# electricRayBot2.net
KiCad netlist of a schematic drawn in EAGLE
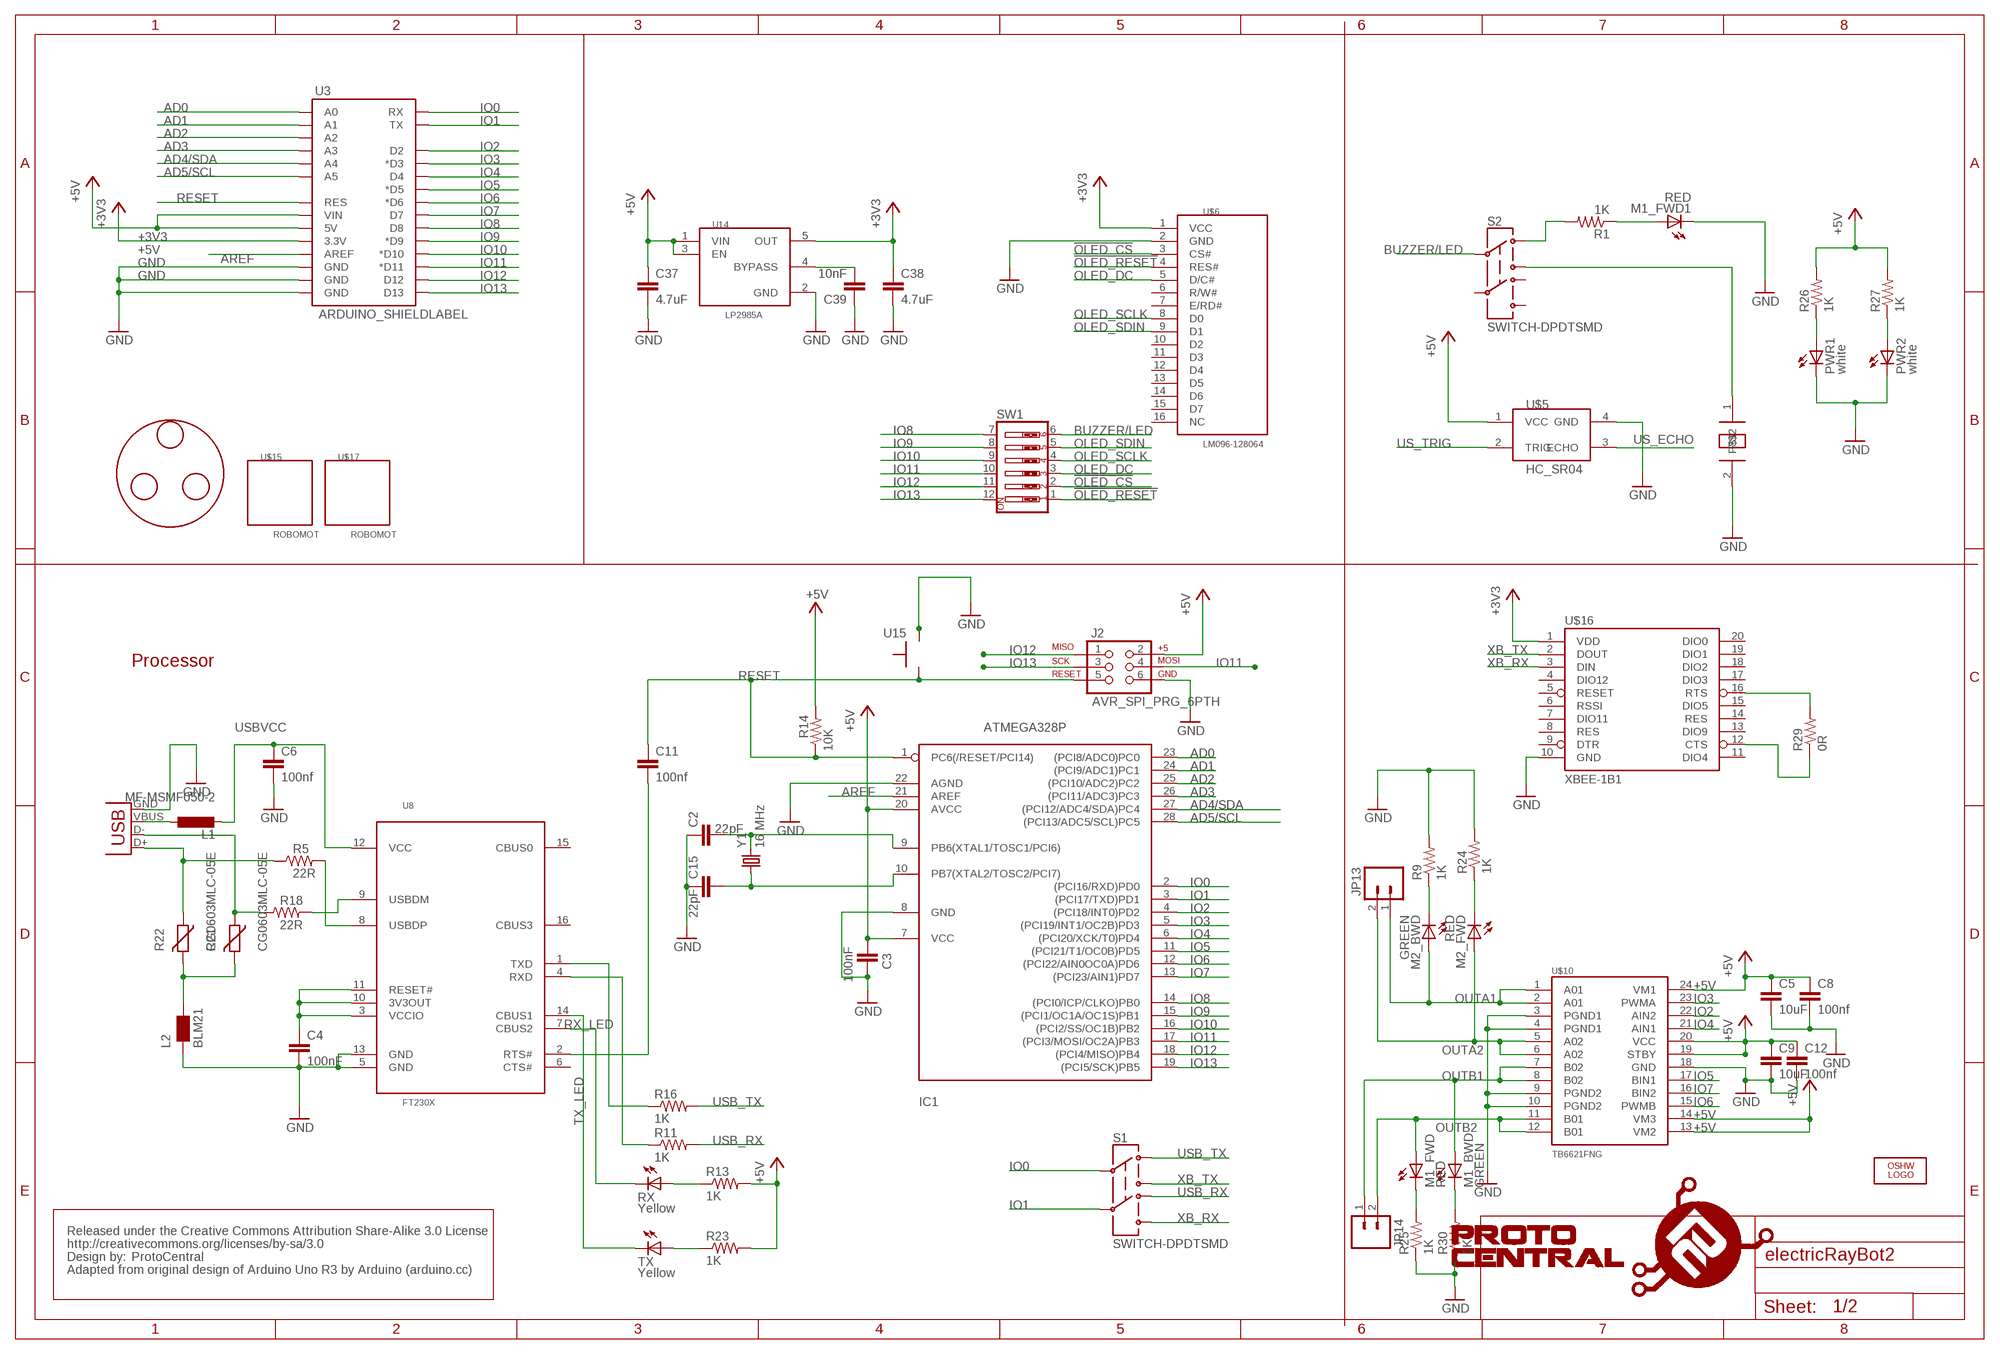
[diagram p0: schematic, sheet 1]
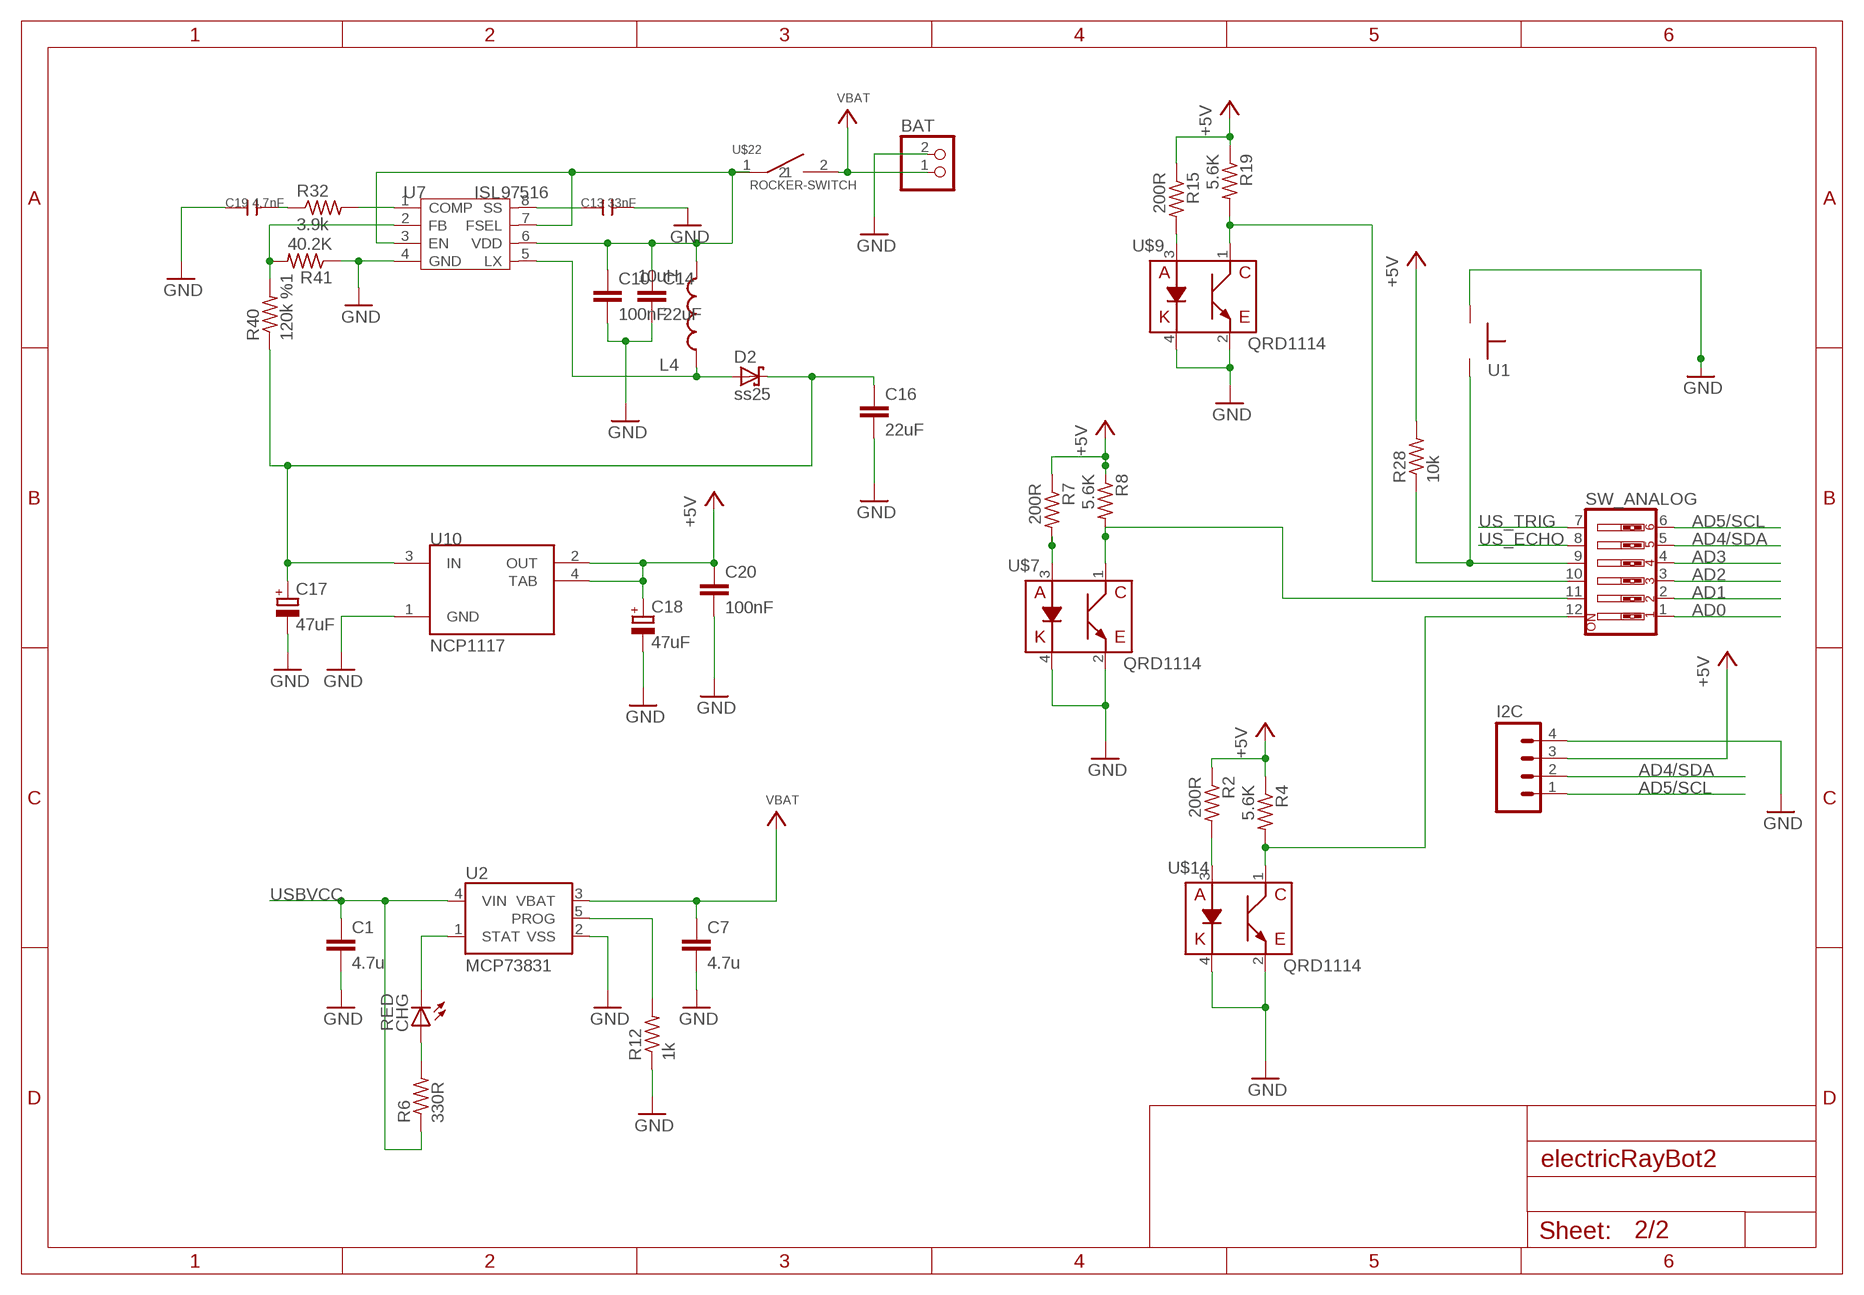
[diagram p1: schematic, sheet 2]

(export (version "E")
  (design (tool "Eeschema 10.0.6"))
  (components
    (comp (ref "BAT")
      (value "JST_2PIN-THM")
      (footprint "eagle-import:JST-PH-2-THM")
      (libsource (lib "eagle-import") (part "JST_2PIN-THM"))
    )
    (comp (ref "C1")
      (value "4.7u")
      (footprint "eagle-import:C0805")
      (libsource (lib "eagle-import") (part "C-EUC0805"))
    )
    (comp (ref "C7")
      (value "4.7u")
      (footprint "eagle-import:C0805")
      (libsource (lib "eagle-import") (part "C-EUC0805"))
    )
    (comp (ref "C10")
      (value "100nF")
      (footprint "eagle-import:C0805")
      (libsource (lib "eagle-import") (part "C-EUC0805"))
    )
    (comp (ref "C13")
      (value "33nF")
      (footprint "eagle-import:C0603")
      (libsource (lib "eagle-import") (part "C-0603"))
    )
    (comp (ref "C14")
      (value "22uF")
      (footprint "eagle-import:C1206")
      (libsource (lib "eagle-import") (part "C-EUC1206"))
    )
    (comp (ref "C16")
      (value "22uF")
      (footprint "eagle-import:C1206")
      (libsource (lib "eagle-import") (part "C-EUC1206"))
    )
    (comp (ref "C17")
      (value "47uF")
      (footprint "eagle-import:PANASONIC_D")
      (libsource (lib "eagle-import") (part "CPOL-EUD"))
    )
    (comp (ref "C18")
      (value "47uF")
      (footprint "eagle-import:PANASONIC_D")
      (libsource (lib "eagle-import") (part "CPOL-EUD"))
    )
    (comp (ref "C19")
      (value "4.7nF")
      (footprint "eagle-import:C0603")
      (libsource (lib "eagle-import") (part "C-0603"))
    )
    (comp (ref "C20")
      (value "100nF")
      (footprint "eagle-import:C0402")
      (libsource (lib "eagle-import") (part "C-EUC0402"))
    )
    (comp (ref "CHG")
      (value "RED")
      (footprint "eagle-import:CHIPLED_0603")
      (libsource (lib "eagle-import") (part "LEDCHIPLED_0603"))
    )
    (comp (ref "D2")
      (value "ss25")
      (footprint "eagle-import:SMB")
      (libsource (lib "eagle-import") (part "SCHOTTKY-DIODESMD"))
    )
    (comp (ref "I2C")
      (value "M04POLAR_LOCK")
      (footprint "eagle-import:MOLEX-1X4_LOCK")
      (libsource (lib "eagle-import") (part "M04POLAR_LOCK"))
    )
    (comp (ref "L4")
      (value "10uH")
      (footprint "eagle-import:CDRH8D43")
      (libsource (lib "eagle-import") (part "CDRH8D43"))
    )
    (comp (ref "R2")
      (value "200R")
      (footprint "eagle-import:R0805")
      (libsource (lib "eagle-import") (part "R-US_R0805"))
    )
    (comp (ref "R4")
      (value "5.6K")
      (footprint "eagle-import:R0805")
      (libsource (lib "eagle-import") (part "R-US_R0805"))
    )
    (comp (ref "R6")
      (value "330R")
      (footprint "eagle-import:R0805")
      (libsource (lib "eagle-import") (part "R-US_R0805"))
    )
    (comp (ref "R7")
      (value "200R")
      (footprint "eagle-import:R0805")
      (libsource (lib "eagle-import") (part "R-US_R0805"))
    )
    (comp (ref "R8")
      (value "5.6K")
      (footprint "eagle-import:R0805")
      (libsource (lib "eagle-import") (part "R-US_R0805"))
    )
    (comp (ref "R12")
      (value "1k")
      (footprint "eagle-import:R0805")
      (libsource (lib "eagle-import") (part "R-US_R0805"))
    )
    (comp (ref "R15")
      (value "200R")
      (footprint "eagle-import:R0805")
      (libsource (lib "eagle-import") (part "R-US_R0805"))
    )
    (comp (ref "R19")
      (value "5.6K")
      (footprint "eagle-import:R0805")
      (libsource (lib "eagle-import") (part "R-US_R0805"))
    )
    (comp (ref "R28")
      (value "10k")
      (footprint "eagle-import:R0805")
      (libsource (lib "eagle-import") (part "R-US_R0805"))
    )
    (comp (ref "R32")
      (value "3.9k")
      (footprint "eagle-import:R0805")
      (libsource (lib "eagle-import") (part "R-US_R0805"))
    )
    (comp (ref "R40")
      (value "120k %1")
      (footprint "eagle-import:R0805")
      (libsource (lib "eagle-import") (part "R-US_R0805"))
    )
    (comp (ref "R41")
      (value "40.2K")
      (footprint "eagle-import:R0805")
      (libsource (lib "eagle-import") (part "R-US_R0805"))
    )
    (comp (ref "SW_ANALOG")
      (value "SW_DIP-6")
      (footprint "eagle-import:EDG-06")
      (libsource (lib "eagle-import") (part "SW_DIP-6"))
    )
    (comp (ref "U$7")
      (value "QRD1114")
      (footprint "eagle-import:QRD1114")
      (libsource (lib "eagle-import") (part "QRD1114"))
    )
    (comp (ref "U$9")
      (value "QRD1114")
      (footprint "eagle-import:QRD1114")
      (libsource (lib "eagle-import") (part "QRD1114"))
    )
    (comp (ref "U$14")
      (value "QRD1114")
      (footprint "eagle-import:QRD1114")
      (libsource (lib "eagle-import") (part "QRD1114"))
    )
    (comp (ref "U$22")
      (value "ROCKER-SWITCH")
      (footprint "eagle-import:SPST(RIGHT-ANGLE)")
      (libsource (lib "eagle-import") (part "ROCKER-SWITCH"))
    )
    (comp (ref "U1")
      (value "EVQQ2")
      (footprint "eagle-import:EVQQ2")
      (libsource (lib "eagle-import") (part "EVQQ2"))
    )
    (comp (ref "U2")
      (value "MCP73831")
      (footprint "eagle-import:SOT23-5")
      (libsource (lib "eagle-import") (part "MCP73831"))
    )
    (comp (ref "U7")
      (value "ISL97516")
      (footprint "eagle-import:MSOP8")
      (libsource (lib "eagle-import") (part "ISL97516"))
    )
    (comp (ref "U10")
      (value "NCP1117")
      (footprint "eagle-import:SOT223")
      (libsource (lib "eagle-import") (part "NCP1117"))
    )
    (comp (ref "C2")
      (value "22pF")
      (footprint "eagle-import:C0402")
      (libsource (lib "eagle-import") (part "C-EUC0402"))
    )
    (comp (ref "C3")
      (value "100nF")
      (footprint "eagle-import:C0805")
      (libsource (lib "eagle-import") (part "C-EUC0805"))
    )
    (comp (ref "C4")
      (value "100nF")
      (footprint "eagle-import:C0805")
      (libsource (lib "eagle-import") (part "C-EUC0805"))
    )
    (comp (ref "C5")
      (value "10uF")
      (footprint "eagle-import:C0805")
      (libsource (lib "eagle-import") (part "C-EUC0805"))
    )
    (comp (ref "C6")
      (value "100nf")
      (footprint "eagle-import:C0805")
      (libsource (lib "eagle-import") (part "C-EUC0805"))
    )
    (comp (ref "C8")
      (value "100nf")
      (footprint "eagle-import:C0805")
      (libsource (lib "eagle-import") (part "C-EUC0805"))
    )
    (comp (ref "C9")
      (value "10uF")
      (footprint "eagle-import:C0805")
      (libsource (lib "eagle-import") (part "C-EUC0805"))
    )
    (comp (ref "C11")
      (value "100nf")
      (footprint "eagle-import:C0805")
      (libsource (lib "eagle-import") (part "C-EUC0805"))
    )
    (comp (ref "C12")
      (value "100nf")
      (footprint "eagle-import:C0805")
      (libsource (lib "eagle-import") (part "C-EUC0805"))
    )
    (comp (ref "C15")
      (value "22pF")
      (footprint "eagle-import:C0402")
      (libsource (lib "eagle-import") (part "C-EUC0402"))
    )
    (comp (ref "C37")
      (value "4.7uF")
      (footprint "eagle-import:C0805")
      (libsource (lib "eagle-import") (part "C-EUC0805"))
    )
    (comp (ref "C38")
      (value "4.7uF")
      (footprint "eagle-import:C0805")
      (libsource (lib "eagle-import") (part "C-EUC0805"))
    )
    (comp (ref "C39")
      (value "10nF")
      (footprint "eagle-import:C0805")
      (libsource (lib "eagle-import") (part "C-EUC0805"))
    )
    (comp (ref "IC1")
      (value "ATMEGA328P")
      (footprint "eagle-import:DIP28")
      (libsource (lib "eagle-import") (part "ATMEGA328P"))
    )
    (comp (ref "J2")
      (value "AVR_SPI_PRG_6PTH")
      (footprint "eagle-import:2X3")
      (libsource (lib "eagle-import") (part "AVR_SPI_PRG_6PTH"))
    )
    (comp (ref "JP13")
      (value "M023.5MM")
      (footprint "eagle-import:SCREWTERMINAL-3.5MM-2")
      (libsource (lib "eagle-import") (part "M023.5MM"))
    )
    (comp (ref "JP14")
      (value "M023.5MM")
      (footprint "eagle-import:SCREWTERMINAL-3.5MM-2")
      (libsource (lib "eagle-import") (part "M023.5MM"))
    )
    (comp (ref "L1")
      (value "MF-MSMF050-2")
      (footprint "eagle-import:L1812")
      (libsource (lib "eagle-import") (part "L-EUL1812"))
    )
    (comp (ref "L2")
      (value "BLM21")
      (footprint "eagle-import:0805")
      (libsource (lib "eagle-import") (part "WE-CBF_0805"))
    )
    (comp (ref "LOGO2")
      (value "OSHW_LOGO_FILLX0350-NT")
      (footprint "eagle-import:OSHW_FILLX350_NOTEXT")
      (libsource (lib "eagle-import") (part "OSHW_LOGO_FILLX0350-NT"))
    )
    (comp (ref "M1_BWD")
      (value "GREEN")
      (footprint "eagle-import:CHIPLED_0603")
      (libsource (lib "eagle-import") (part "LEDCHIPLED_0603"))
    )
    (comp (ref "M1_FWD")
      (value "RED")
      (footprint "eagle-import:CHIPLED_0603")
      (libsource (lib "eagle-import") (part "LEDCHIPLED_0603"))
    )
    (comp (ref "M1_FWD1")
      (value "RED")
      (footprint "eagle-import:CHIPLED_0603")
      (libsource (lib "eagle-import") (part "LEDCHIPLED_0603"))
    )
    (comp (ref "M2_BWD")
      (value "GREEN")
      (footprint "eagle-import:CHIPLED_0603")
      (libsource (lib "eagle-import") (part "LEDCHIPLED_0603"))
    )
    (comp (ref "M2_FWD")
      (value "RED")
      (footprint "eagle-import:CHIPLED_0603")
      (libsource (lib "eagle-import") (part "LEDCHIPLED_0603"))
    )
    (comp (ref "PWR1")
      (value "white")
      (footprint "eagle-import:LED-0603")
      (libsource (lib "eagle-import") (part "LED0603"))
    )
    (comp (ref "PWR2")
      (value "white")
      (footprint "eagle-import:LED-0603")
      (libsource (lib "eagle-import") (part "LED0603"))
    )
    (comp (ref "R1")
      (value "1K")
      (footprint "eagle-import:R0805")
      (libsource (lib "eagle-import") (part "R-US_R0805"))
    )
    (comp (ref "R5")
      (value "22R")
      (footprint "eagle-import:R0805")
      (libsource (lib "eagle-import") (part "R-US_R0805"))
    )
    (comp (ref "R9")
      (value "1K")
      (footprint "eagle-import:R0805")
      (libsource (lib "eagle-import") (part "R-US_R0805"))
    )
    (comp (ref "R11")
      (value "1K")
      (footprint "eagle-import:R0805")
      (libsource (lib "eagle-import") (part "R-US_R0805"))
    )
    (comp (ref "R13")
      (value "1K")
      (footprint "eagle-import:R0805")
      (libsource (lib "eagle-import") (part "R-US_R0805"))
    )
    (comp (ref "R14")
      (value "10K")
      (footprint "eagle-import:R0805")
      (libsource (lib "eagle-import") (part "R-US_R0805"))
    )
    (comp (ref "R16")
      (value "1K")
      (footprint "eagle-import:R0805")
      (libsource (lib "eagle-import") (part "R-US_R0805"))
    )
    (comp (ref "R18")
      (value "22R")
      (footprint "eagle-import:R0805")
      (libsource (lib "eagle-import") (part "R-US_R0805"))
    )
    (comp (ref "R21")
      (value "CG0603MLC-05E")
      (footprint "eagle-import:CT_CN0603")
      (libsource (lib "eagle-import") (part "VARISTORCN0603"))
    )
    (comp (ref "R22")
      (value "CG0603MLC-05E")
      (footprint "eagle-import:CT_CN0603")
      (libsource (lib "eagle-import") (part "VARISTORCN0603"))
    )
    (comp (ref "R23")
      (value "1K")
      (footprint "eagle-import:R0805")
      (libsource (lib "eagle-import") (part "R-US_R0805"))
    )
    (comp (ref "R24")
      (value "1K")
      (footprint "eagle-import:R0805")
      (libsource (lib "eagle-import") (part "R-US_R0805"))
    )
    (comp (ref "R25")
      (value "1K")
      (footprint "eagle-import:R0805")
      (libsource (lib "eagle-import") (part "R-US_R0805"))
    )
    (comp (ref "R26")
      (value "1K")
      (footprint "eagle-import:R0805")
      (libsource (lib "eagle-import") (part "R-US_R0805"))
    )
    (comp (ref "R27")
      (value "1K")
      (footprint "eagle-import:R0805")
      (libsource (lib "eagle-import") (part "R-US_R0805"))
    )
    (comp (ref "R29")
      (value "0R")
      (footprint "eagle-import:R0805")
      (libsource (lib "eagle-import") (part "R-US_R0805"))
    )
    (comp (ref "R30")
      (value "1K")
      (footprint "eagle-import:R0805")
      (libsource (lib "eagle-import") (part "R-US_R0805"))
    )
    (comp (ref "RX")
      (value "Yellow")
      (footprint "eagle-import:CHIPLED_0603")
      (libsource (lib "eagle-import") (part "LEDCHIPLED_0603"))
    )
    (comp (ref "S1")
      (value "SWITCH-DPDTSMD")
      (footprint "eagle-import:AYZ0202")
      (libsource (lib "eagle-import") (part "SWITCH-DPDTSMD"))
    )
    (comp (ref "S2")
      (value "SWITCH-DPDTSMD")
      (footprint "eagle-import:AYZ0202")
      (libsource (lib "eagle-import") (part "SWITCH-DPDTSMD"))
    )
    (comp (ref "SW1")
      (value "SW_DIP-6")
      (footprint "eagle-import:EDG-06")
      (libsource (lib "eagle-import") (part "SW_DIP-6"))
    )
    (comp (ref "TX")
      (value "Yellow")
      (footprint "eagle-import:CHIPLED_0603")
      (libsource (lib "eagle-import") (part "LEDCHIPLED_0603"))
    )
    (comp (ref "U$1")
      (value "CREATIVE_COMMONS")
      (footprint "eagle-import:CREATIVE_COMMONS")
      (libsource (lib "eagle-import") (part "CREATIVE_COMMONS"))
    )
    (comp (ref "U$4")
      (value "PS1740")
      (footprint "eagle-import:PS02")
      (libsource (lib "eagle-import") (part "PS1740"))
    )
    (comp (ref "U$5")
      (value "HC_SR04")
      (footprint "eagle-import:ULTRA")
      (libsource (lib "eagle-import") (part "HC_SR04"))
    )
    (comp (ref "U$6")
      (value "LM096-128064")
      (footprint "eagle-import:LM096-128064(OLED)")
      (libsource (lib "eagle-import") (part "LM096-128064"))
    )
    (comp (ref "U$10")
      (value "TB6621FNG")
      (footprint "eagle-import:SSOP24")
      (libsource (lib "eagle-import") (part "TB6621FNG"))
    )
    (comp (ref "U$15")
      (value "ROBOMOT")
      (footprint "eagle-import:ROBOMOT")
      (libsource (lib "eagle-import") (part "ROBOMOT"))
    )
    (comp (ref "U$16")
      (value "XBEE-1B1")
      (footprint "eagle-import:XBEE-1")
      (libsource (lib "eagle-import") (part "XBEE-1B1"))
    )
    (comp (ref "U$17")
      (value "ROBOMOT")
      (footprint "eagle-import:ROBOMOT")
      (libsource (lib "eagle-import") (part "ROBOMOT"))
    )
    (comp (ref "U$18")
      (value "PROTY-LOGO")
      (footprint "eagle-import:LOGO-PROTY")
      (libsource (lib "eagle-import") (part "PROTY-LOGO"))
    )
    (comp (ref "U$20")
      (value "MOTO")
      (footprint "eagle-import:MOTO")
      (libsource (lib "eagle-import") (part "MOTO"))
    )
    (comp (ref "U3")
      (value "ARDUINO_SHIELDLABEL")
      (footprint "eagle-import:DUEMILANOVE_SHIELD")
      (libsource (lib "eagle-import") (part "ARDUINO_SHIELDLABEL"))
    )
    (comp (ref "U8")
      (value "FT230X")
      (footprint "eagle-import:SSOP_16")
      (libsource (lib "eagle-import") (part "FT230X"))
    )
    (comp (ref "U14")
      (value "LP2985A")
      (footprint "eagle-import:SOT23-5")
      (libsource (lib "eagle-import") (part "LP2985A"))
    )
    (comp (ref "U15")
      (value "EVQQ2")
      (footprint "eagle-import:EVQQ2")
      (libsource (lib "eagle-import") (part "EVQQ2"))
    )
    (comp (ref "X1")
      (value "USBPTH")
      (footprint "eagle-import:USB-B-PTH")
      (libsource (lib "eagle-import") (part "USBPTH"))
    )
    (comp (ref "Y1")
      (value "16 MHz")
      (footprint "eagle-import:HC49US")
      (libsource (lib "eagle-import") (part "CRYSTALHC49US"))
    )
  )
  (nets
    (net (code "1") (name "+3V3") (class "Default")
      (node (ref "C38") (pin "1") (pinfunction "1_1") (pintype "passive"))
      (node (ref "U$16") (pin "1") (pinfunction "VDD_1") (pintype "power_in"))
      (node (ref "U$6") (pin "1") (pinfunction "VCC_1") (pintype "bidirectional"))
      (node (ref "U14") (pin "5") (pinfunction "OUT_5") (pintype "bidirectional"))
      (node (ref "U3") (pin "3.3V") (pinfunction "3.3V_3.3V") (pintype "bidirectional"))
    )
    (net (code "2") (name "+5V") (class "Default")
      (node (ref "C12") (pin "1") (pinfunction "1_1") (pintype "passive"))
      (node (ref "C18") (pin "+") (pinfunction "+_+") (pintype "passive"))
      (node (ref "C20") (pin "1") (pinfunction "1_1") (pintype "passive"))
      (node (ref "C3") (pin "1") (pinfunction "1_1") (pintype "passive"))
      (node (ref "C37") (pin "1") (pinfunction "1_1") (pintype "passive"))
      (node (ref "C5") (pin "1") (pinfunction "1_1") (pintype "passive"))
      (node (ref "C8") (pin "1") (pinfunction "1_1") (pintype "passive"))
      (node (ref "C9") (pin "1") (pinfunction "1_1") (pintype "passive"))
      (node (ref "I2C") (pin "3") (pinfunction "3_3") (pintype "passive"))
      (node (ref "IC1") (pin "20") (pinfunction "AVCC_20") (pintype "bidirectional"))
      (node (ref "IC1") (pin "7") (pinfunction "VCC_7") (pintype "bidirectional"))
      (node (ref "J2") (pin "2") (pinfunction "2_2") (pintype "passive"))
      (node (ref "R13") (pin "2") (pinfunction "2_2") (pintype "passive"))
      (node (ref "R14") (pin "2") (pinfunction "2_2") (pintype "passive"))
      (node (ref "R15") (pin "1") (pinfunction "1_1") (pintype "passive"))
      (node (ref "R19") (pin "1") (pinfunction "1_1") (pintype "passive"))
      (node (ref "R2") (pin "1") (pinfunction "1_1") (pintype "passive"))
      (node (ref "R23") (pin "2") (pinfunction "2_2") (pintype "passive"))
      (node (ref "R26") (pin "2") (pinfunction "2_2") (pintype "passive"))
      (node (ref "R27") (pin "2") (pinfunction "2_2") (pintype "passive"))
      (node (ref "R28") (pin "2") (pinfunction "2_2") (pintype "passive"))
      (node (ref "R4") (pin "1") (pinfunction "1_1") (pintype "passive"))
      (node (ref "R7") (pin "1") (pinfunction "1_1") (pintype "passive"))
      (node (ref "R8") (pin "1") (pinfunction "1_1") (pintype "passive"))
      (node (ref "U$10") (pin "13") (pinfunction "VM2_13") (pintype "bidirectional"))
      (node (ref "U$10") (pin "14") (pinfunction "VM3_14") (pintype "bidirectional"))
      (node (ref "U$10") (pin "19") (pinfunction "STBY_19") (pintype "bidirectional"))
      (node (ref "U$10") (pin "20") (pinfunction "VCC_20") (pintype "bidirectional"))
      (node (ref "U$10") (pin "24") (pinfunction "VM1_24") (pintype "bidirectional"))
      (node (ref "U$5") (pin "1") (pinfunction "VCC_1") (pintype "bidirectional"))
      (node (ref "U10") (pin "2") (pinfunction "OUT_2") (pintype "bidirectional"))
      (node (ref "U10") (pin "4") (pinfunction "TAB_4") (pintype "bidirectional"))
      (node (ref "U14") (pin "1") (pinfunction "VIN_1") (pintype "bidirectional"))
      (node (ref "U14") (pin "3") (pinfunction "EN_3") (pintype "bidirectional"))
      (node (ref "U3") (pin "5V") (pinfunction "5V_5V") (pintype "bidirectional"))
      (node (ref "U3") (pin "VIN") (pinfunction "VIN_VIN") (pintype "bidirectional"))
    )
    (net (code "3") (name "AD0") (class "Default")
      (node (ref "IC1") (pin "23") (pinfunction "(PCI8/ADC0)PC0_23") (pintype "bidirectional"))
      (node (ref "SW_ANALOG") (pin "1") (pinfunction "1_1") (pintype "passive"))
      (node (ref "U3") (pin "A0") (pinfunction "A0_A0") (pintype "bidirectional"))
    )
    (net (code "4") (name "AD1") (class "Default")
      (node (ref "IC1") (pin "24") (pinfunction "(PCI9/ADC1)PC1_24") (pintype "bidirectional"))
      (node (ref "SW_ANALOG") (pin "2") (pinfunction "2_2") (pintype "passive"))
      (node (ref "U3") (pin "A1") (pinfunction "A1_A1") (pintype "bidirectional"))
    )
    (net (code "5") (name "AD2") (class "Default")
      (node (ref "IC1") (pin "25") (pinfunction "(PCI10/ADC2)PC2_25") (pintype "bidirectional"))
      (node (ref "SW_ANALOG") (pin "3") (pinfunction "3_3") (pintype "passive"))
      (node (ref "U3") (pin "A2") (pinfunction "A2_A2") (pintype "bidirectional"))
    )
    (net (code "6") (name "AD3") (class "Default")
      (node (ref "IC1") (pin "26") (pinfunction "(PCI11/ADC3)PC3_26") (pintype "bidirectional"))
      (node (ref "SW_ANALOG") (pin "4") (pinfunction "4_4") (pintype "passive"))
      (node (ref "U3") (pin "A3") (pinfunction "A3_A3") (pintype "bidirectional"))
    )
    (net (code "7") (name "AD4{slash}SDA") (class "Default")
      (node (ref "I2C") (pin "2") (pinfunction "2_2") (pintype "passive"))
      (node (ref "IC1") (pin "27") (pinfunction "(PCI12/ADC4/SDA)PC4_27") (pintype "bidirectional"))
      (node (ref "SW_ANALOG") (pin "5") (pinfunction "5_5") (pintype "passive"))
      (node (ref "U3") (pin "A4") (pinfunction "A4_A4") (pintype "bidirectional"))
    )
    (net (code "8") (name "AD5{slash}SCL") (class "Default")
      (node (ref "I2C") (pin "1") (pinfunction "1_1") (pintype "passive"))
      (node (ref "IC1") (pin "28") (pinfunction "(PCI13/ADC5/SCL)PC5_28") (pintype "bidirectional"))
      (node (ref "SW_ANALOG") (pin "6") (pinfunction "6_6") (pintype "passive"))
      (node (ref "U3") (pin "A5") (pinfunction "A5_A5") (pintype "bidirectional"))
    )
    (net (code "9") (name "AREF") (class "Default")
      (node (ref "IC1") (pin "21") (pinfunction "AREF_21") (pintype "bidirectional"))
      (node (ref "U3") (pin "AREF") (pinfunction "AREF_AREF") (pintype "bidirectional"))
    )
    (net (code "10") (name "BUZZER{slash}LED") (class "Default")
      (node (ref "S2") (pin "2") (pinfunction "2_2") (pintype "bidirectional"))
      (node (ref "SW1") (pin "6") (pinfunction "6_6") (pintype "passive"))
    )
    (net (code "11") (name "GND") (class "Default")
      (node (ref "BAT") (pin "2") (pinfunction "1_2") (pintype "passive"))
      (node (ref "C1") (pin "2") (pinfunction "2_2") (pintype "passive"))
      (node (ref "C10") (pin "2") (pinfunction "2_2") (pintype "passive"))
      (node (ref "C12") (pin "2") (pinfunction "2_2") (pintype "passive"))
      (node (ref "C13") (pin "2") (pinfunction "2_2") (pintype "passive"))
      (node (ref "C14") (pin "2") (pinfunction "2_2") (pintype "passive"))
      (node (ref "C15") (pin "1") (pinfunction "1_1") (pintype "passive"))
      (node (ref "C16") (pin "2") (pinfunction "2_2") (pintype "passive"))
      (node (ref "C17") (pin "-") (pinfunction "-_-") (pintype "passive"))
      (node (ref "C18") (pin "-") (pinfunction "-_-") (pintype "passive"))
      (node (ref "C19") (pin "1") (pinfunction "1_1") (pintype "passive"))
      (node (ref "C2") (pin "1") (pinfunction "1_1") (pintype "passive"))
      (node (ref "C20") (pin "2") (pinfunction "2_2") (pintype "passive"))
      (node (ref "C3") (pin "2") (pinfunction "2_2") (pintype "passive"))
      (node (ref "C37") (pin "2") (pinfunction "2_2") (pintype "passive"))
      (node (ref "C38") (pin "2") (pinfunction "2_2") (pintype "passive"))
      (node (ref "C39") (pin "1") (pinfunction "1_1") (pintype "passive"))
      (node (ref "C4") (pin "2") (pinfunction "2_2") (pintype "passive"))
      (node (ref "C5") (pin "2") (pinfunction "2_2") (pintype "passive"))
      (node (ref "C6") (pin "2") (pinfunction "2_2") (pintype "passive"))
      (node (ref "C7") (pin "2") (pinfunction "2_2") (pintype "passive"))
      (node (ref "C8") (pin "2") (pinfunction "2_2") (pintype "passive"))
      (node (ref "C9") (pin "2") (pinfunction "2_2") (pintype "passive"))
      (node (ref "I2C") (pin "4") (pinfunction "4_4") (pintype "passive"))
      (node (ref "IC1") (pin "22") (pinfunction "AGND_22") (pintype "bidirectional"))
      (node (ref "IC1") (pin "8") (pinfunction "GND_8") (pintype "bidirectional"))
      (node (ref "J2") (pin "6") (pinfunction "6_6") (pintype "passive"))
      (node (ref "L2") (pin "1") (pinfunction "1_1") (pintype "passive"))
      (node (ref "M1_FWD1") (pin "C") (pinfunction "C_C") (pintype "passive"))
      (node (ref "PWR1") (pin "C") (pinfunction "C_C") (pintype "passive"))
      (node (ref "PWR2") (pin "C") (pinfunction "C_C") (pintype "passive"))
      (node (ref "R12") (pin "1") (pinfunction "1_1") (pintype "passive"))
      (node (ref "R24") (pin "2") (pinfunction "2_2") (pintype "passive"))
      (node (ref "R25") (pin "1") (pinfunction "1_1") (pintype "passive"))
      (node (ref "R30") (pin "1") (pinfunction "1_1") (pintype "passive"))
      (node (ref "R41") (pin "1") (pinfunction "1_1") (pintype "passive"))
      (node (ref "R9") (pin "2") (pinfunction "2_2") (pintype "passive"))
      (node (ref "U$10") (pin "10") (pinfunction "PGND2_10") (pintype "bidirectional"))
      (node (ref "U$10") (pin "18") (pinfunction "GND_18") (pintype "bidirectional"))
      (node (ref "U$10") (pin "3") (pinfunction "PGND1_3") (pintype "bidirectional"))
      (node (ref "U$10") (pin "4") (pinfunction "PGND1_4") (pintype "bidirectional"))
      (node (ref "U$10") (pin "9") (pinfunction "PGND2_9") (pintype "bidirectional"))
      (node (ref "U$14") (pin "2") (pinfunction "C_2") (pintype "bidirectional"))
      (node (ref "U$14") (pin "4") (pinfunction "K_4") (pintype "bidirectional"))
      (node (ref "U$16") (pin "10") (pinfunction "GND_10") (pintype "power_in"))
      (node (ref "U$4") (pin "2") (pinfunction "P$2_2") (pintype "bidirectional"))
      (node (ref "U$5") (pin "4") (pinfunction "GND_4") (pintype "bidirectional"))
      (node (ref "U$6") (pin "2") (pinfunction "GND_2") (pintype "bidirectional"))
      (node (ref "U$7") (pin "2") (pinfunction "C_2") (pintype "bidirectional"))
      (node (ref "U$7") (pin "4") (pinfunction "K_4") (pintype "bidirectional"))
      (node (ref "U$9") (pin "2") (pinfunction "C_2") (pintype "bidirectional"))
      (node (ref "U$9") (pin "4") (pinfunction "K_4") (pintype "bidirectional"))
      (node (ref "U1") (pin "P$1") (pinfunction "P$1_P$1") (pintype "bidirectional"))
      (node (ref "U10") (pin "1") (pinfunction "GND_1") (pintype "bidirectional"))
      (node (ref "U14") (pin "2") (pinfunction "GND_2") (pintype "bidirectional"))
      (node (ref "U15") (pin "P$3") (pinfunction "P$2_P$3") (pintype "bidirectional"))
      (node (ref "U2") (pin "2") (pinfunction "VSS_2") (pintype "power_in"))
      (node (ref "U3") (pin "GND@0") (pinfunction "GND_GND@0") (pintype "bidirectional"))
      (node (ref "U3") (pin "GND@1") (pinfunction "GND_GND@1") (pintype "bidirectional"))
      (node (ref "U3") (pin "GND@2") (pinfunction "GND_GND@2") (pintype "bidirectional"))
      (node (ref "U7") (pin "4") (pinfunction "GND_4") (pintype "power_in"))
      (node (ref "U8") (pin "13") (pinfunction "GND_13") (pintype "bidirectional"))
      (node (ref "U8") (pin "5") (pinfunction "GND_5") (pintype "bidirectional"))
      (node (ref "X1") (pin "GND") (pinfunction "GND_GND") (pintype "bidirectional"))
    )
    (net (code "12") (name "IO0") (class "Default")
      (node (ref "IC1") (pin "2") (pinfunction "(PCI16/RXD)PD0_2") (pintype "bidirectional"))
      (node (ref "S1") (pin "2") (pinfunction "2_2") (pintype "bidirectional"))
      (node (ref "U3") (pin "RX") (pinfunction "RX_RX") (pintype "bidirectional"))
    )
    (net (code "13") (name "IO1") (class "Default")
      (node (ref "IC1") (pin "3") (pinfunction "(PCI17/TXD)PD1_3") (pintype "bidirectional"))
      (node (ref "S1") (pin "5") (pinfunction "5_5") (pintype "bidirectional"))
      (node (ref "U3") (pin "TX") (pinfunction "TX_TX") (pintype "bidirectional"))
    )
    (net (code "14") (name "IO2") (class "Default")
      (node (ref "IC1") (pin "4") (pinfunction "(PCI18/INT0)PD2_4") (pintype "bidirectional"))
      (node (ref "U$10") (pin "22") (pinfunction "AIN2_22") (pintype "bidirectional"))
      (node (ref "U3") (pin "D2") (pinfunction "D2_D2") (pintype "bidirectional"))
    )
    (net (code "15") (name "IO3") (class "Default")
      (node (ref "IC1") (pin "5") (pinfunction "(PCI19/INT1/OC2B)PD3_5") (pintype "bidirectional"))
      (node (ref "U$10") (pin "23") (pinfunction "PWMA_23") (pintype "bidirectional"))
      (node (ref "U3") (pin "D3") (pinfunction "*D3_D3") (pintype "bidirectional"))
    )
    (net (code "16") (name "IO4") (class "Default")
      (node (ref "IC1") (pin "6") (pinfunction "(PCI20/XCK/T0)PD4_6") (pintype "bidirectional"))
      (node (ref "U$10") (pin "21") (pinfunction "AIN1_21") (pintype "bidirectional"))
      (node (ref "U3") (pin "D4") (pinfunction "D4_D4") (pintype "bidirectional"))
    )
    (net (code "17") (name "IO5") (class "Default")
      (node (ref "IC1") (pin "11") (pinfunction "(PCI21/T1/OC0B)PD5_11") (pintype "bidirectional"))
      (node (ref "U$10") (pin "17") (pinfunction "BIN1_17") (pintype "bidirectional"))
      (node (ref "U3") (pin "D5") (pinfunction "*D5_D5") (pintype "bidirectional"))
    )
    (net (code "18") (name "IO6") (class "Default")
      (node (ref "IC1") (pin "12") (pinfunction "(PCI22/AIN0OC0A)PD6_12") (pintype "bidirectional"))
      (node (ref "U$10") (pin "15") (pinfunction "PWMB_15") (pintype "bidirectional"))
      (node (ref "U3") (pin "D6") (pinfunction "*D6_D6") (pintype "bidirectional"))
    )
    (net (code "19") (name "IO7") (class "Default")
      (node (ref "IC1") (pin "13") (pinfunction "(PCI23/AIN1)PD7_13") (pintype "bidirectional"))
      (node (ref "U$10") (pin "16") (pinfunction "BIN2_16") (pintype "bidirectional"))
      (node (ref "U3") (pin "D7") (pinfunction "D7_D7") (pintype "bidirectional"))
    )
    (net (code "20") (name "IO8") (class "Default")
      (node (ref "IC1") (pin "14") (pinfunction "(PCI0/ICP/CLKO)PB0_14") (pintype "bidirectional"))
      (node (ref "SW1") (pin "7") (pinfunction "7_7") (pintype "passive"))
      (node (ref "U3") (pin "D8") (pinfunction "D8_D8") (pintype "bidirectional"))
    )
    (net (code "21") (name "IO9") (class "Default")
      (node (ref "IC1") (pin "15") (pinfunction "(PCI1/OC1A/OC1S)PB1_15") (pintype "bidirectional"))
      (node (ref "SW1") (pin "8") (pinfunction "8_8") (pintype "passive"))
      (node (ref "U3") (pin "D9") (pinfunction "*D9_D9") (pintype "bidirectional"))
    )
    (net (code "22") (name "IO10") (class "Default")
      (node (ref "IC1") (pin "16") (pinfunction "(PCI2/SS/OC1B)PB2_16") (pintype "bidirectional"))
      (node (ref "SW1") (pin "9") (pinfunction "9_9") (pintype "passive"))
      (node (ref "U3") (pin "D10") (pinfunction "*D10_D10") (pintype "bidirectional"))
    )
    (net (code "23") (name "IO11") (class "Default")
      (node (ref "IC1") (pin "17") (pinfunction "(PCI3/MOSI/OC2A)PB3_17") (pintype "bidirectional"))
      (node (ref "J2") (pin "4") (pinfunction "4_4") (pintype "passive"))
      (node (ref "SW1") (pin "10") (pinfunction "10_10") (pintype "passive"))
      (node (ref "U3") (pin "D11") (pinfunction "*D11_D11") (pintype "bidirectional"))
    )
    (net (code "24") (name "IO12") (class "Default")
      (node (ref "IC1") (pin "18") (pinfunction "(PCI4/MISO)PB4_18") (pintype "bidirectional"))
      (node (ref "J2") (pin "1") (pinfunction "1_1") (pintype "passive"))
      (node (ref "SW1") (pin "11") (pinfunction "11_11") (pintype "passive"))
      (node (ref "U3") (pin "D12") (pinfunction "D12_D12") (pintype "bidirectional"))
    )
    (net (code "25") (name "IO13") (class "Default")
      (node (ref "IC1") (pin "19") (pinfunction "(PCI5/SCK)PB5_19") (pintype "bidirectional"))
      (node (ref "J2") (pin "3") (pinfunction "3_3") (pintype "passive"))
      (node (ref "SW1") (pin "12") (pinfunction "12_12") (pintype "passive"))
      (node (ref "U3") (pin "D13") (pinfunction "D13_D13") (pintype "bidirectional"))
    )
    (net (code "26") (name "Net-(C19-Pad2)") (class "Default")
      (node (ref "C19") (pin "2") (pinfunction "2_2") (pintype "passive"))
      (node (ref "R32") (pin "1") (pinfunction "1_1") (pintype "passive"))
    )
    (net (code "27") (name "Net-(CHG-PadA)") (class "Default")
      (node (ref "CHG") (pin "A") (pinfunction "A_A") (pintype "passive"))
      (node (ref "R6") (pin "2") (pinfunction "2_2") (pintype "passive"))
    )
    (net (code "28") (name "Net-(IC1-PB6(XTAL1{slash}TOSC1{slash}PCI6))") (class "Default")
      (node (ref "C2") (pin "2") (pinfunction "2_2") (pintype "passive"))
      (node (ref "IC1") (pin "9") (pinfunction "PB6(XTAL1/TOSC1/PCI6)_9") (pintype "bidirectional"))
      (node (ref "Y1") (pin "2") (pinfunction "2_2") (pintype "passive"))
    )
    (net (code "29") (name "Net-(IC1-PB7(XTAL2{slash}TOSC2{slash}PCI7))") (class "Default")
      (node (ref "C15") (pin "2") (pinfunction "2_2") (pintype "passive"))
      (node (ref "IC1") (pin "10") (pinfunction "PB7(XTAL2/TOSC2/PCI7)_10") (pintype "bidirectional"))
      (node (ref "Y1") (pin "1") (pinfunction "1_1") (pintype "passive"))
    )
    (net (code "30") (name "Net-(L1-Pad1)") (class "Default")
      (node (ref "L1") (pin "1") (pinfunction "1_1") (pintype "passive"))
      (node (ref "X1") (pin "VBUS") (pinfunction "VBUS_VBUS") (pintype "bidirectional"))
    )
    (net (code "31") (name "Net-(L2-Pad2)") (class "Default")
      (node (ref "L2") (pin "2") (pinfunction "2_2") (pintype "passive"))
      (node (ref "R21") (pin "2") (pinfunction "2_2") (pintype "passive"))
      (node (ref "R22") (pin "2") (pinfunction "2_2") (pintype "passive"))
    )
    (net (code "32") (name "Net-(L4-1)") (class "Default")
      (node (ref "D2") (pin "A") (pinfunction "A_A") (pintype "passive"))
      (node (ref "L4") (pin "P$1") (pinfunction "1_P$1") (pintype "passive"))
      (node (ref "U7") (pin "5") (pinfunction "LX_5") (pintype "output"))
    )
    (net (code "33") (name "Net-(L4-2)") (class "Default")
      (node (ref "C10") (pin "1") (pinfunction "1_1") (pintype "passive"))
      (node (ref "C14") (pin "1") (pinfunction "1_1") (pintype "passive"))
      (node (ref "L4") (pin "P$2") (pinfunction "2_P$2") (pintype "passive"))
      (node (ref "U$22") (pin "1") (pinfunction "1_1") (pintype "bidirectional"))
      (node (ref "U7") (pin "3") (pinfunction "EN_3") (pintype "input"))
      (node (ref "U7") (pin "6") (pinfunction "VDD_6") (pintype "power_in"))
      (node (ref "U7") (pin "7") (pinfunction "FSEL_7") (pintype "bidirectional"))
    )
    (net (code "34") (name "Net-(M1_BWD-PadC)") (class "Default")
      (node (ref "M1_BWD") (pin "C") (pinfunction "C_C") (pintype "passive"))
      (node (ref "R30") (pin "2") (pinfunction "2_2") (pintype "passive"))
    )
    (net (code "35") (name "Net-(M1_FWD-PadC)") (class "Default")
      (node (ref "M1_FWD") (pin "C") (pinfunction "C_C") (pintype "passive"))
      (node (ref "R25") (pin "2") (pinfunction "2_2") (pintype "passive"))
    )
    (net (code "36") (name "Net-(M1_FWD1-PadA)") (class "Default")
      (node (ref "M1_FWD1") (pin "A") (pinfunction "A_A") (pintype "passive"))
      (node (ref "R1") (pin "1") (pinfunction "1_1") (pintype "passive"))
    )
    (net (code "37") (name "Net-(M2_BWD-PadC)") (class "Default")
      (node (ref "M2_BWD") (pin "C") (pinfunction "C_C") (pintype "passive"))
      (node (ref "R9") (pin "1") (pinfunction "1_1") (pintype "passive"))
    )
    (net (code "38") (name "Net-(M2_FWD-PadC)") (class "Default")
      (node (ref "M2_FWD") (pin "C") (pinfunction "C_C") (pintype "passive"))
      (node (ref "R24") (pin "1") (pinfunction "1_1") (pintype "passive"))
    )
    (net (code "39") (name "Net-(PWR1-PadA)") (class "Default")
      (node (ref "PWR1") (pin "A") (pinfunction "A_A") (pintype "passive"))
      (node (ref "R26") (pin "1") (pinfunction "1_1") (pintype "passive"))
    )
    (net (code "40") (name "Net-(PWR2-PadA)") (class "Default")
      (node (ref "PWR2") (pin "A") (pinfunction "A_A") (pintype "passive"))
      (node (ref "R27") (pin "1") (pinfunction "1_1") (pintype "passive"))
    )
    (net (code "41") (name "Net-(R1-Pad2)") (class "Default")
      (node (ref "R1") (pin "2") (pinfunction "2_2") (pintype "passive"))
      (node (ref "S2") (pin "1") (pinfunction "1_1") (pintype "bidirectional"))
    )
    (net (code "42") (name "Net-(R13-Pad1)") (class "Default")
      (node (ref "R13") (pin "1") (pinfunction "1_1") (pintype "passive"))
      (node (ref "RX") (pin "A") (pinfunction "A_A") (pintype "passive"))
    )
    (net (code "43") (name "Net-(R18-Pad1)") (class "Default")
      (node (ref "R18") (pin "1") (pinfunction "1_1") (pintype "passive"))
      (node (ref "R21") (pin "1") (pinfunction "1_1") (pintype "passive"))
      (node (ref "X1") (pin "D-") (pinfunction "D-_D-") (pintype "bidirectional"))
    )
    (net (code "44") (name "Net-(R22-Pad1)") (class "Default")
      (node (ref "R22") (pin "1") (pinfunction "1_1") (pintype "passive"))
      (node (ref "R5") (pin "1") (pinfunction "1_1") (pintype "passive"))
      (node (ref "X1") (pin "D+") (pinfunction "D+_D+") (pintype "bidirectional"))
    )
    (net (code "45") (name "Net-(R23-Pad1)") (class "Default")
      (node (ref "R23") (pin "1") (pinfunction "1_1") (pintype "passive"))
      (node (ref "TX") (pin "A") (pinfunction "A_A") (pintype "passive"))
    )
    (net (code "46") (name "Net-(U$4-P$1)") (class "Default")
      (node (ref "S2") (pin "3") (pinfunction "3_3") (pintype "bidirectional"))
      (node (ref "U$4") (pin "1") (pinfunction "P$1_1") (pintype "bidirectional"))
    )
    (net (code "47") (name "Net-(U$7-A)") (class "Default")
      (node (ref "R7") (pin "2") (pinfunction "2_2") (pintype "passive"))
      (node (ref "U$7") (pin "3") (pinfunction "A_3") (pintype "bidirectional"))
    )
    (net (code "48") (name "Net-(U$7-E)") (class "Default")
      (node (ref "R8") (pin "2") (pinfunction "2_2") (pintype "passive"))
      (node (ref "SW_ANALOG") (pin "11") (pinfunction "11_11") (pintype "passive"))
      (node (ref "U$7") (pin "1") (pinfunction "E_1") (pintype "bidirectional"))
    )
    (net (code "49") (name "Net-(U$9-A)") (class "Default")
      (node (ref "R15") (pin "2") (pinfunction "2_2") (pintype "passive"))
      (node (ref "U$9") (pin "3") (pinfunction "A_3") (pintype "bidirectional"))
    )
    (net (code "50") (name "Net-(U$9-E)") (class "Default")
      (node (ref "R19") (pin "2") (pinfunction "2_2") (pintype "passive"))
      (node (ref "SW_ANALOG") (pin "10") (pinfunction "10_10") (pintype "passive"))
      (node (ref "U$9") (pin "1") (pinfunction "E_1") (pintype "bidirectional"))
    )
    (net (code "51") (name "Net-(U$14-A)") (class "Default")
      (node (ref "R2") (pin "2") (pinfunction "2_2") (pintype "passive"))
      (node (ref "U$14") (pin "3") (pinfunction "A_3") (pintype "bidirectional"))
    )
    (net (code "52") (name "Net-(U$14-E)") (class "Default")
      (node (ref "R4") (pin "2") (pinfunction "2_2") (pintype "passive"))
      (node (ref "SW_ANALOG") (pin "12") (pinfunction "12_12") (pintype "passive"))
      (node (ref "U$14") (pin "1") (pinfunction "E_1") (pintype "bidirectional"))
    )
    (net (code "53") (name "Net-(U$16-CTS)") (class "Default")
      (node (ref "R29") (pin "1") (pinfunction "1_1") (pintype "passive"))
      (node (ref "U$16") (pin "12") (pinfunction "CTS_12") (pintype "output"))
    )
    (net (code "54") (name "Net-(U$16-RTS)") (class "Default")
      (node (ref "R29") (pin "2") (pinfunction "2_2") (pintype "passive"))
      (node (ref "U$16") (pin "16") (pinfunction "RTS_16") (pintype "input"))
    )
    (net (code "55") (name "Net-(U1-P$2)") (class "Default")
      (node (ref "R28") (pin "1") (pinfunction "1_1") (pintype "passive"))
      (node (ref "SW_ANALOG") (pin "9") (pinfunction "9_9") (pintype "passive"))
      (node (ref "U1") (pin "P$3") (pinfunction "P$2_P$3") (pintype "bidirectional"))
    )
    (net (code "56") (name "Net-(U2-PROG)") (class "Default")
      (node (ref "R12") (pin "2") (pinfunction "2_2") (pintype "passive"))
      (node (ref "U2") (pin "5") (pinfunction "PROG_5") (pintype "input"))
    )
    (net (code "57") (name "Net-(U2-STAT)") (class "Default")
      (node (ref "CHG") (pin "C") (pinfunction "C_C") (pintype "passive"))
      (node (ref "U2") (pin "1") (pinfunction "STAT_1") (pintype "output"))
    )
    (net (code "58") (name "Net-(U7-COMP)") (class "Default")
      (node (ref "R32") (pin "2") (pinfunction "2_2") (pintype "passive"))
      (node (ref "U7") (pin "1") (pinfunction "COMP_1") (pintype "bidirectional"))
    )
    (net (code "59") (name "Net-(U7-FB)") (class "Default")
      (node (ref "R40") (pin "2") (pinfunction "2_2") (pintype "passive"))
      (node (ref "R41") (pin "2") (pinfunction "2_2") (pintype "passive"))
      (node (ref "U7") (pin "2") (pinfunction "FB_2") (pintype "input"))
    )
    (net (code "60") (name "Net-(U7-SS)") (class "Default")
      (node (ref "C13") (pin "1") (pinfunction "1_1") (pintype "passive"))
      (node (ref "U7") (pin "8") (pinfunction "SS_8") (pintype "bidirectional"))
    )
    (net (code "61") (name "Net-(U8-3V3OUT)") (class "Default")
      (node (ref "C4") (pin "1") (pinfunction "1_1") (pintype "passive"))
      (node (ref "U8") (pin "10") (pinfunction "3V3OUT_10") (pintype "bidirectional"))
      (node (ref "U8") (pin "11") (pinfunction "RESET#_11") (pintype "bidirectional"))
      (node (ref "U8") (pin "3") (pinfunction "VCCIO_3") (pintype "bidirectional"))
    )
    (net (code "62") (name "Net-(U8-RTS#)") (class "Default")
      (node (ref "C11") (pin "2") (pinfunction "2_2") (pintype "passive"))
      (node (ref "U8") (pin "2") (pinfunction "RTS#_2") (pintype "bidirectional"))
    )
    (net (code "63") (name "Net-(U8-RXD)") (class "Default")
      (node (ref "R11") (pin "1") (pinfunction "1_1") (pintype "passive"))
      (node (ref "U8") (pin "4") (pinfunction "RXD_4") (pintype "bidirectional"))
    )
    (net (code "64") (name "Net-(U8-TXD)") (class "Default")
      (node (ref "R16") (pin "1") (pinfunction "1_1") (pintype "passive"))
      (node (ref "U8") (pin "1") (pinfunction "TXD_1") (pintype "bidirectional"))
    )
    (net (code "65") (name "Net-(U8-USBDM)") (class "Default")
      (node (ref "R18") (pin "2") (pinfunction "2_2") (pintype "passive"))
      (node (ref "U8") (pin "9") (pinfunction "USBDM_9") (pintype "bidirectional"))
    )
    (net (code "66") (name "Net-(U8-USBDP)") (class "Default")
      (node (ref "R5") (pin "2") (pinfunction "2_2") (pintype "passive"))
      (node (ref "U8") (pin "8") (pinfunction "USBDP_8") (pintype "bidirectional"))
    )
    (net (code "67") (name "Net-(U10-IN)") (class "Default")
      (node (ref "C16") (pin "1") (pinfunction "1_1") (pintype "passive"))
      (node (ref "C17") (pin "+") (pinfunction "+_+") (pintype "passive"))
      (node (ref "D2") (pin "C") (pinfunction "C_C") (pintype "passive"))
      (node (ref "R40") (pin "1") (pinfunction "1_1") (pintype "passive"))
      (node (ref "U10") (pin "3") (pinfunction "IN_3") (pintype "bidirectional"))
    )
    (net (code "68") (name "Net-(U14-BYPASS)") (class "Default")
      (node (ref "C39") (pin "2") (pinfunction "2_2") (pintype "passive"))
      (node (ref "U14") (pin "4") (pinfunction "BYPASS_4") (pintype "bidirectional"))
    )
    (net (code "69") (name "OLED_DC") (class "Default")
      (node (ref "SW1") (pin "3") (pinfunction "3_3") (pintype "passive"))
      (node (ref "U$6") (pin "5") (pinfunction "D/C#_5") (pintype "bidirectional"))
    )
    (net (code "70") (name "OLED_SCLK") (class "Default")
      (node (ref "SW1") (pin "4") (pinfunction "4_4") (pintype "passive"))
      (node (ref "U$6") (pin "8") (pinfunction "D0_8") (pintype "bidirectional"))
    )
    (net (code "71") (name "OLED_SDIN") (class "Default")
      (node (ref "SW1") (pin "5") (pinfunction "5_5") (pintype "passive"))
      (node (ref "U$6") (pin "9") (pinfunction "D1_9") (pintype "bidirectional"))
    )
    (net (code "72") (name "OUTA1") (class "Default")
      (node (ref "JP13") (pin "1") (pinfunction "1_1") (pintype "passive"))
      (node (ref "M2_BWD") (pin "A") (pinfunction "A_A") (pintype "passive"))
      (node (ref "U$10") (pin "1") (pinfunction "A01_1") (pintype "bidirectional"))
      (node (ref "U$10") (pin "2") (pinfunction "A01_2") (pintype "bidirectional"))
    )
    (net (code "73") (name "OUTA2") (class "Default")
      (node (ref "JP13") (pin "2") (pinfunction "2_2") (pintype "passive"))
      (node (ref "M2_FWD") (pin "A") (pinfunction "A_A") (pintype "passive"))
      (node (ref "U$10") (pin "5") (pinfunction "A02_5") (pintype "bidirectional"))
      (node (ref "U$10") (pin "6") (pinfunction "A02_6") (pintype "bidirectional"))
    )
    (net (code "74") (name "OUTB1") (class "Default")
      (node (ref "JP14") (pin "1") (pinfunction "1_1") (pintype "passive"))
      (node (ref "M1_BWD") (pin "A") (pinfunction "A_A") (pintype "passive"))
      (node (ref "U$10") (pin "7") (pinfunction "B02_7") (pintype "bidirectional"))
      (node (ref "U$10") (pin "8") (pinfunction "B02_8") (pintype "bidirectional"))
    )
    (net (code "75") (name "OUTB2") (class "Default")
      (node (ref "JP14") (pin "2") (pinfunction "2_2") (pintype "passive"))
      (node (ref "M1_FWD") (pin "A") (pinfunction "A_A") (pintype "passive"))
      (node (ref "U$10") (pin "11") (pinfunction "B01_11") (pintype "bidirectional"))
      (node (ref "U$10") (pin "12") (pinfunction "B01_12") (pintype "bidirectional"))
    )
    (net (code "76") (name "RESET") (class "Default")
      (node (ref "C11") (pin "1") (pinfunction "1_1") (pintype "passive"))
      (node (ref "IC1") (pin "1") (pinfunction "PC6(/RESET/PCI14)_1") (pintype "bidirectional"))
      (node (ref "J2") (pin "5") (pinfunction "5_5") (pintype "passive"))
      (node (ref "R14") (pin "1") (pinfunction "1_1") (pintype "passive"))
      (node (ref "U15") (pin "P$1") (pinfunction "P$1_P$1") (pintype "bidirectional"))
      (node (ref "U3") (pin "RES") (pinfunction "RES_RES") (pintype "bidirectional"))
    )
    (net (code "77") (name "RX_LED") (class "Default")
      (node (ref "RX") (pin "C") (pinfunction "C_C") (pintype "passive"))
      (node (ref "U8") (pin "7") (pinfunction "CBUS2_7") (pintype "bidirectional"))
    )
    (net (code "78") (name "TX_LED") (class "Default")
      (node (ref "TX") (pin "C") (pinfunction "C_C") (pintype "passive"))
      (node (ref "U8") (pin "14") (pinfunction "CBUS1_14") (pintype "bidirectional"))
    )
    (net (code "79") (name "USBVCC") (class "Default")
      (node (ref "C1") (pin "1") (pinfunction "1_1") (pintype "passive"))
      (node (ref "C6") (pin "1") (pinfunction "1_1") (pintype "passive"))
      (node (ref "L1") (pin "2") (pinfunction "2_2") (pintype "passive"))
      (node (ref "R6") (pin "1") (pinfunction "1_1") (pintype "passive"))
      (node (ref "U2") (pin "4") (pinfunction "VIN_4") (pintype "power_in"))
      (node (ref "U8") (pin "12") (pinfunction "VCC_12") (pintype "bidirectional"))
    )
    (net (code "80") (name "USB_RX") (class "Default")
      (node (ref "R11") (pin "2") (pinfunction "2_2") (pintype "passive"))
      (node (ref "S1") (pin "4") (pinfunction "4_4") (pintype "bidirectional"))
    )
    (net (code "81") (name "USB_TX") (class "Default")
      (node (ref "R16") (pin "2") (pinfunction "2_2") (pintype "passive"))
      (node (ref "S1") (pin "1") (pinfunction "1_1") (pintype "bidirectional"))
    )
    (net (code "82") (name "US_ECHO") (class "Default")
      (node (ref "SW_ANALOG") (pin "8") (pinfunction "8_8") (pintype "passive"))
      (node (ref "U$5") (pin "3") (pinfunction "ECHO_3") (pintype "bidirectional"))
    )
    (net (code "83") (name "US_TRIG") (class "Default")
      (node (ref "SW_ANALOG") (pin "7") (pinfunction "7_7") (pintype "passive"))
      (node (ref "U$5") (pin "2") (pinfunction "TRIG_2") (pintype "bidirectional"))
    )
    (net (code "84") (name "VBAT") (class "Default")
      (node (ref "BAT") (pin "1") (pinfunction "2_1") (pintype "passive"))
      (node (ref "C7") (pin "1") (pinfunction "1_1") (pintype "passive"))
      (node (ref "U$22") (pin "2") (pinfunction "2_2") (pintype "bidirectional"))
      (node (ref "U2") (pin "3") (pinfunction "VBAT_3") (pintype "power_in"))
    )
    (net (code "85") (name "XB_RX") (class "Default")
      (node (ref "S1") (pin "6") (pinfunction "6_6") (pintype "bidirectional"))
      (node (ref "U$16") (pin "3") (pinfunction "DIN_3") (pintype "input"))
    )
    (net (code "86") (name "XB_TX") (class "Default")
      (node (ref "S1") (pin "3") (pinfunction "3_3") (pintype "bidirectional"))
      (node (ref "U$16") (pin "2") (pinfunction "DOUT_2") (pintype "output"))
    )
    (net (code "87") (name "unconnected-(S2-Pad4)") (class "Default")
      (node (ref "S2") (pin "4") (pinfunction "4_4") (pintype "bidirectional"))
    )
    (net (code "88") (name "unconnected-(S2-Pad5)") (class "Default")
      (node (ref "S2") (pin "5") (pinfunction "5_5") (pintype "bidirectional"))
    )
    (net (code "89") (name "unconnected-(S2-Pad6)") (class "Default")
      (node (ref "S2") (pin "6") (pinfunction "6_6") (pintype "bidirectional"))
    )
    (net (code "90") (name "unconnected-(U$6-D2-Pad10)") (class "Default")
      (node (ref "U$6") (pin "10") (pinfunction "D2_10") (pintype "bidirectional"))
    )
    (net (code "91") (name "unconnected-(U$6-D3-Pad11)") (class "Default")
      (node (ref "U$6") (pin "11") (pinfunction "D3_11") (pintype "bidirectional"))
    )
    (net (code "92") (name "unconnected-(U$6-D4-Pad12)") (class "Default")
      (node (ref "U$6") (pin "12") (pinfunction "D4_12") (pintype "bidirectional"))
    )
    (net (code "93") (name "unconnected-(U$6-D5-Pad13)") (class "Default")
      (node (ref "U$6") (pin "13") (pinfunction "D5_13") (pintype "bidirectional"))
    )
    (net (code "94") (name "unconnected-(U$6-D6-Pad14)") (class "Default")
      (node (ref "U$6") (pin "14") (pinfunction "D6_14") (pintype "bidirectional"))
    )
    (net (code "95") (name "unconnected-(U$6-D7-Pad15)") (class "Default")
      (node (ref "U$6") (pin "15") (pinfunction "D7_15") (pintype "bidirectional"))
    )
    (net (code "96") (name "unconnected-(U$6-E{slash}RD#-Pad7)") (class "Default")
      (node (ref "U$6") (pin "7") (pinfunction "E/RD#_7") (pintype "bidirectional"))
    )
    (net (code "97") (name "unconnected-(U$6-NC-Pad16)") (class "Default")
      (node (ref "U$6") (pin "16") (pinfunction "NC_16") (pintype "bidirectional"))
    )
    (net (code "98") (name "unconnected-(U$6-R{slash}W#-Pad6)") (class "Default")
      (node (ref "U$6") (pin "6") (pinfunction "R/W#_6") (pintype "bidirectional"))
    )
    (net (code "99") (name "unconnected-(U$16-DIO0-Pad20)") (class "Default")
      (node (ref "U$16") (pin "20") (pinfunction "DIO0_20") (pintype "bidirectional"))
    )
    (net (code "100") (name "unconnected-(U$16-DIO1-Pad19)") (class "Default")
      (node (ref "U$16") (pin "19") (pinfunction "DIO1_19") (pintype "bidirectional"))
    )
    (net (code "101") (name "unconnected-(U$16-DIO2-Pad18)") (class "Default")
      (node (ref "U$16") (pin "18") (pinfunction "DIO2_18") (pintype "bidirectional"))
    )
    (net (code "102") (name "unconnected-(U$16-DIO3-Pad17)") (class "Default")
      (node (ref "U$16") (pin "17") (pinfunction "DIO3_17") (pintype "bidirectional"))
    )
    (net (code "103") (name "unconnected-(U$16-DIO4-Pad11)") (class "Default")
      (node (ref "U$16") (pin "11") (pinfunction "DIO4_11") (pintype "bidirectional"))
    )
    (net (code "104") (name "unconnected-(U$16-DIO5-Pad15)") (class "Default")
      (node (ref "U$16") (pin "15") (pinfunction "DIO5_15") (pintype "bidirectional"))
    )
    (net (code "105") (name "unconnected-(U$16-DIO9-Pad13)") (class "Default")
      (node (ref "U$16") (pin "13") (pinfunction "DIO9_13") (pintype "bidirectional"))
    )
    (net (code "106") (name "unconnected-(U$16-DIO11-Pad7)") (class "Default")
      (node (ref "U$16") (pin "7") (pinfunction "DIO11_7") (pintype "bidirectional"))
    )
    (net (code "107") (name "unconnected-(U$16-DIO12-Pad4)") (class "Default")
      (node (ref "U$16") (pin "4") (pinfunction "DIO12_4") (pintype "bidirectional"))
    )
    (net (code "108") (name "unconnected-(U$16-DTR-Pad9)") (class "Default")
      (node (ref "U$16") (pin "9") (pinfunction "DTR_9") (pintype "bidirectional"))
    )
    (net (code "109") (name "unconnected-(U$16-RES-Pad8)") (class "Default")
      (node (ref "U$16") (pin "8") (pinfunction "RES_8") (pintype "bidirectional"))
    )
    (net (code "110") (name "unconnected-(U$16-RES-Pad14)") (class "Default")
      (node (ref "U$16") (pin "14") (pinfunction "RES_14") (pintype "bidirectional"))
    )
    (net (code "111") (name "unconnected-(U$16-RESET-Pad5)") (class "Default")
      (node (ref "U$16") (pin "5") (pinfunction "RESET_5") (pintype "input"))
    )
    (net (code "112") (name "unconnected-(U$16-RSSI-Pad6)") (class "Default")
      (node (ref "U$16") (pin "6") (pinfunction "RSSI_6") (pintype "bidirectional"))
    )
    (net (code "113") (name "unconnected-(U8-CBUS0-Pad15)") (class "Default")
      (node (ref "U8") (pin "15") (pinfunction "CBUS0_15") (pintype "bidirectional"))
    )
    (net (code "114") (name "unconnected-(U8-CBUS3-Pad16)") (class "Default")
      (node (ref "U8") (pin "16") (pinfunction "CBUS3_16") (pintype "bidirectional"))
    )
    (net (code "115") (name "unconnected-(U8-CTS#-Pad6)") (class "Default")
      (node (ref "U8") (pin "6") (pinfunction "CTS#_6") (pintype "bidirectional"))
    )
    (net (code "116") (name "~{OLED_CS}") (class "Default")
      (node (ref "SW1") (pin "2") (pinfunction "2_2") (pintype "passive"))
      (node (ref "U$6") (pin "3") (pinfunction "CS#_3") (pintype "bidirectional"))
    )
    (net (code "117") (name "~{OLED_RESET}") (class "Default")
      (node (ref "SW1") (pin "1") (pinfunction "1_1") (pintype "passive"))
      (node (ref "U$6") (pin "4") (pinfunction "RES#_4") (pintype "bidirectional"))
    )
  )
)
